# tricorder.net
KiCad netlist of a schematic drawn in EAGLE
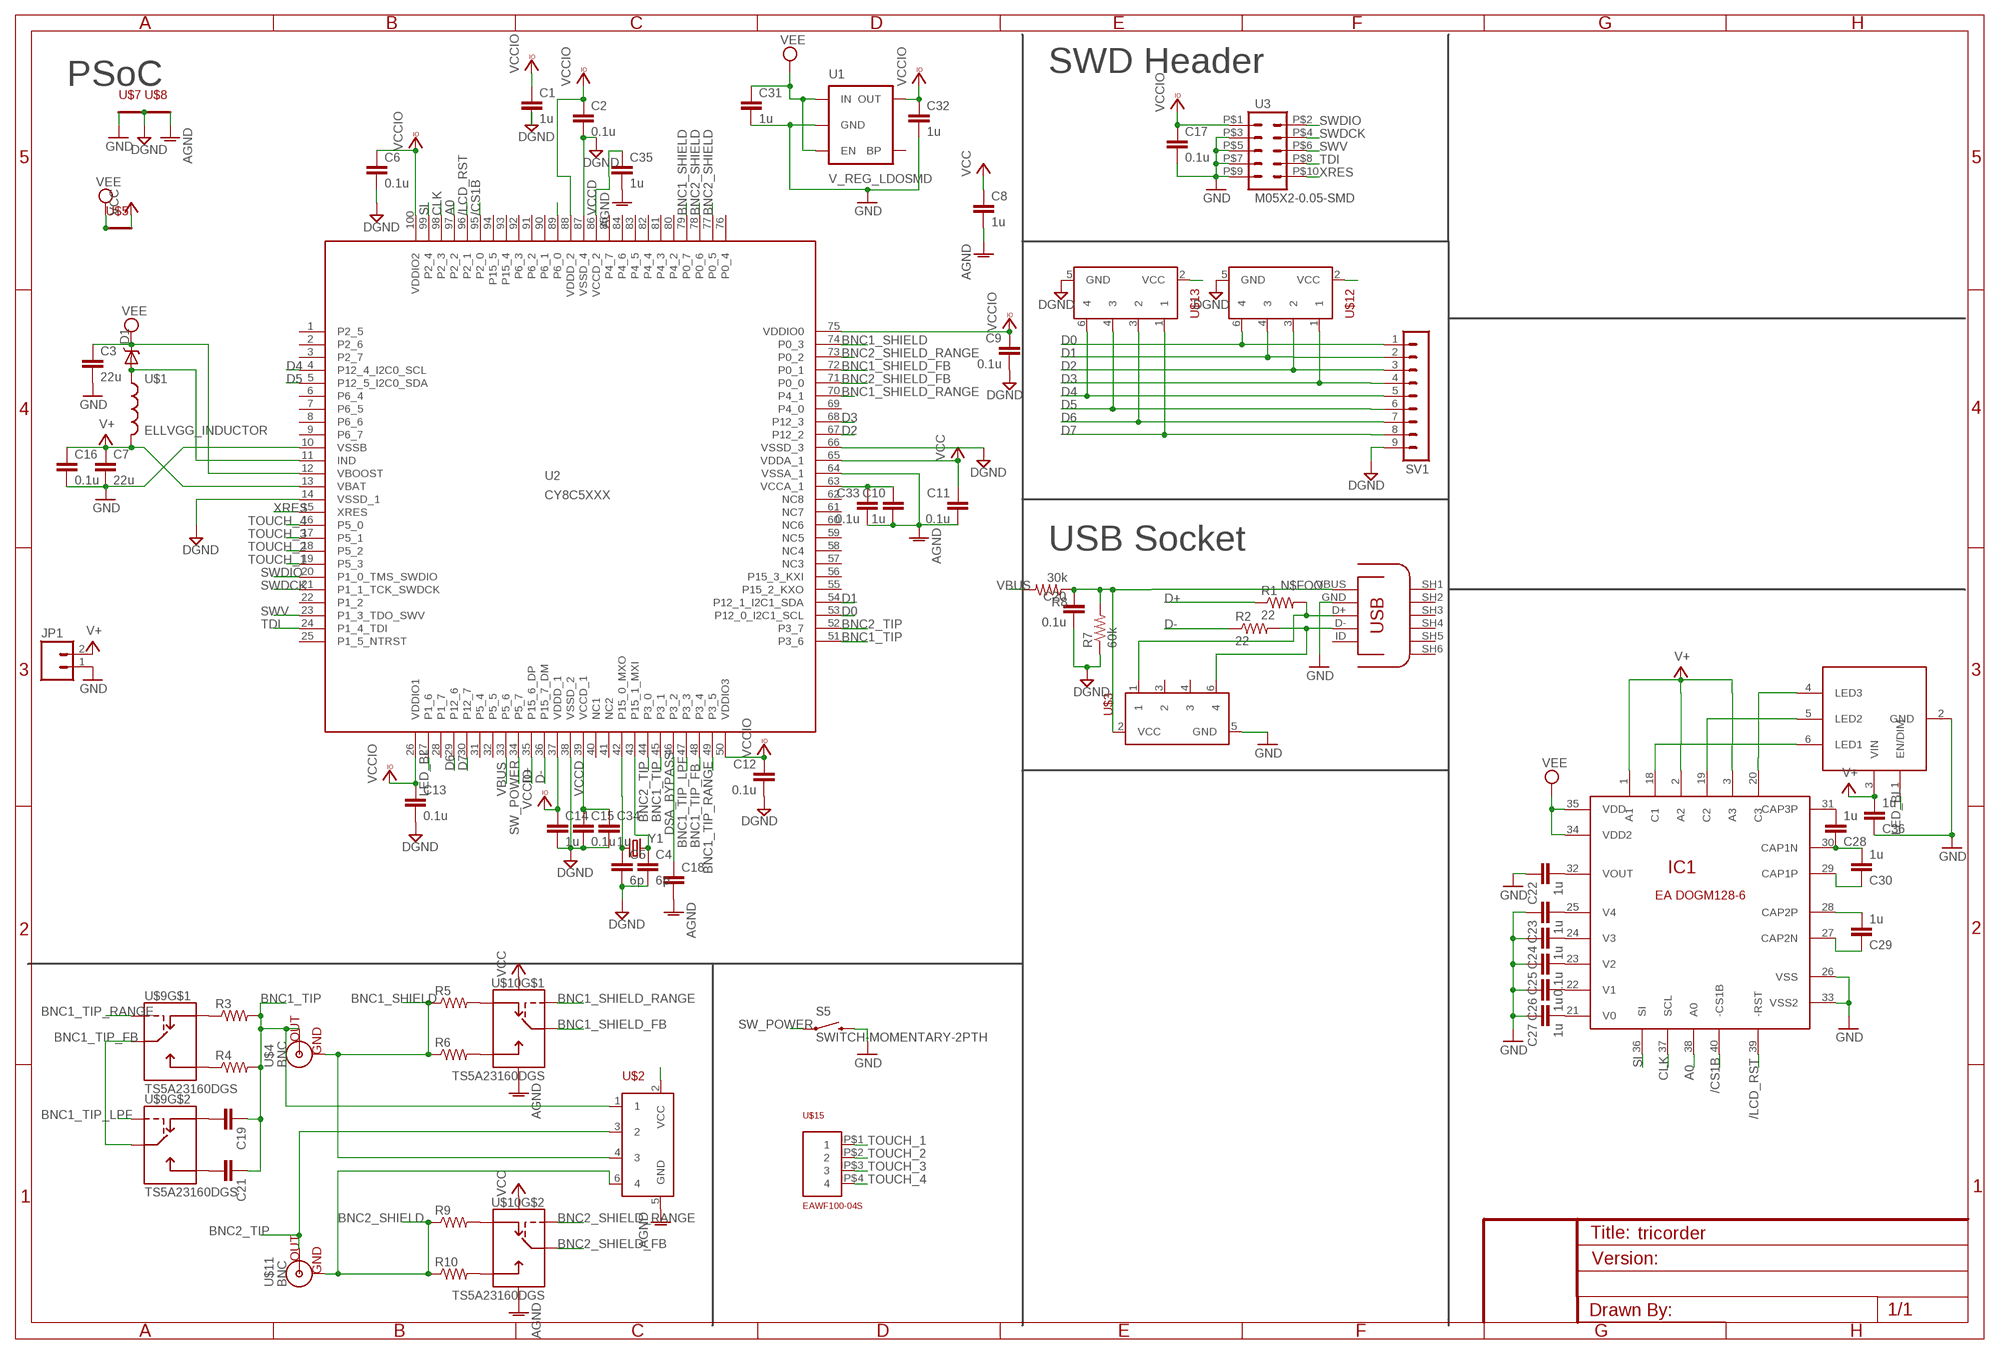
[diagram p0: schematic, sheet 1]

(export (version "E")
  (design (tool "Eeschema 10.0.6"))
  (components
    (comp (ref "C1")
      (value "1u")
      (footprint "eagle-import:0603-CAP")
      (libsource (lib "eagle-import") (part "CAP0603-CAP"))
    )
    (comp (ref "C2")
      (value "0.1u")
      (footprint "eagle-import:0603-CAP")
      (libsource (lib "eagle-import") (part "CAP0603-CAP"))
    )
    (comp (ref "C3")
      (value "22u")
      (footprint "eagle-import:0805")
      (libsource (lib "eagle-import") (part "CAP0805"))
    )
    (comp (ref "C4")
      (value "6p")
      (footprint "eagle-import:0603-CAP")
      (libsource (lib "eagle-import") (part "CAP0603-CAP"))
    )
    (comp (ref "C5")
      (value "6p")
      (footprint "eagle-import:0603-CAP")
      (libsource (lib "eagle-import") (part "CAP0603-CAP"))
    )
    (comp (ref "C6")
      (value "0.1u")
      (footprint "eagle-import:C0603K")
      (libsource (lib "eagle-import") (part "C-EUC0603K"))
    )
    (comp (ref "C7")
      (value "22u")
      (footprint "eagle-import:0805")
      (libsource (lib "eagle-import") (part "CAP0805"))
    )
    (comp (ref "C8")
      (value "1u")
      (footprint "eagle-import:0603-CAP")
      (libsource (lib "eagle-import") (part "CAP0603-CAP"))
    )
    (comp (ref "C9")
      (value "0.1u")
      (footprint "eagle-import:0603-CAP")
      (libsource (lib "eagle-import") (part "CAP0603-CAP"))
    )
    (comp (ref "C10")
      (value "1u")
      (footprint "eagle-import:0603-CAP")
      (libsource (lib "eagle-import") (part "CAP0603-CAP"))
    )
    (comp (ref "C11")
      (value "0.1u")
      (footprint "eagle-import:0603-CAP")
      (libsource (lib "eagle-import") (part "CAP0603-CAP"))
    )
    (comp (ref "C12")
      (value "0.1u")
      (footprint "eagle-import:C0603K")
      (libsource (lib "eagle-import") (part "C-EUC0603K"))
    )
    (comp (ref "C13")
      (value "0.1u")
      (footprint "eagle-import:C0603K")
      (libsource (lib "eagle-import") (part "C-EUC0603K"))
    )
    (comp (ref "C14")
      (value "1u")
      (footprint "eagle-import:0603-CAP")
      (libsource (lib "eagle-import") (part "CAP0603-CAP"))
    )
    (comp (ref "C15")
      (value "0.1u")
      (footprint "eagle-import:0603-CAP")
      (libsource (lib "eagle-import") (part "CAP0603-CAP"))
    )
    (comp (ref "C16")
      (value "0.1u")
      (footprint "eagle-import:0603-CAP")
      (libsource (lib "eagle-import") (part "CAP0603-CAP"))
    )
    (comp (ref "C17")
      (value "0.1u")
      (footprint "eagle-import:C0603K")
      (libsource (lib "eagle-import") (part "C-EUC0603K"))
    )
    (comp (ref "C18")
      (value "CAP0805")
      (footprint "eagle-import:0805")
      (libsource (lib "eagle-import") (part "CAP0805"))
    )
    (comp (ref "C19")
      (value "CAP0603-CAP")
      (footprint "eagle-import:0603-CAP")
      (libsource (lib "eagle-import") (part "CAP0603-CAP"))
    )
    (comp (ref "C20")
      (value "0.1u")
      (footprint "eagle-import:0603-CAP")
      (libsource (lib "eagle-import") (part "CAP0603-CAP"))
    )
    (comp (ref "C21")
      (value "CAP0603-CAP")
      (footprint "eagle-import:0603-CAP")
      (libsource (lib "eagle-import") (part "CAP0603-CAP"))
    )
    (comp (ref "C22")
      (value "1u")
      (footprint "eagle-import:C0603K")
      (libsource (lib "eagle-import") (part "C-EUC0603K"))
    )
    (comp (ref "C23")
      (value "1u")
      (footprint "eagle-import:C0603K")
      (libsource (lib "eagle-import") (part "C-EUC0603K"))
    )
    (comp (ref "C24")
      (value "1u")
      (footprint "eagle-import:C0603K")
      (libsource (lib "eagle-import") (part "C-EUC0603K"))
    )
    (comp (ref "C25")
      (value "0.1u")
      (footprint "eagle-import:C0603K")
      (libsource (lib "eagle-import") (part "C-EUC0603K"))
    )
    (comp (ref "C26")
      (value "1u")
      (footprint "eagle-import:C0603K")
      (libsource (lib "eagle-import") (part "C-EUC0603K"))
    )
    (comp (ref "C27")
      (value "1u")
      (footprint "eagle-import:C0603K")
      (libsource (lib "eagle-import") (part "C-EUC0603K"))
    )
    (comp (ref "C28")
      (value "1u")
      (footprint "eagle-import:C0603K")
      (libsource (lib "eagle-import") (part "C-EUC0603K"))
    )
    (comp (ref "C29")
      (value "1u")
      (footprint "eagle-import:C0603K")
      (libsource (lib "eagle-import") (part "C-EUC0603K"))
    )
    (comp (ref "C30")
      (value "1u")
      (footprint "eagle-import:C0603K")
      (libsource (lib "eagle-import") (part "C-EUC0603K"))
    )
    (comp (ref "C31")
      (value "1u")
      (footprint "eagle-import:0603-CAP")
      (libsource (lib "eagle-import") (part "CAP0603-CAP"))
    )
    (comp (ref "C32")
      (value "1u")
      (footprint "eagle-import:0603-CAP")
      (libsource (lib "eagle-import") (part "CAP0603-CAP"))
    )
    (comp (ref "C33")
      (value "0.1u")
      (footprint "eagle-import:0603-CAP")
      (libsource (lib "eagle-import") (part "CAP0603-CAP"))
    )
    (comp (ref "C34")
      (value "1u")
      (footprint "eagle-import:0603-CAP")
      (libsource (lib "eagle-import") (part "CAP0603-CAP"))
    )
    (comp (ref "C35")
      (value "1u")
      (footprint "eagle-import:0603-CAP")
      (libsource (lib "eagle-import") (part "CAP0603-CAP"))
    )
    (comp (ref "C36")
      (value "1u")
      (footprint "eagle-import:C0603K")
      (libsource (lib "eagle-import") (part "C-EUC0603K"))
    )
    (comp (ref "D1")
      (value "DIODE-SCHOTTKY_")
      (footprint "eagle-import:SMA-DIODE")
      (libsource (lib "eagle-import") (part "DIODE-SCHOTTKY_"))
    )
    (comp (ref "IC1")
      (value "EADOGM128")
      (footprint "eagle-import:EADOGM128")
      (libsource (lib "eagle-import") (part "EADOGM128"))
    )
    (comp (ref "JP1")
      (value "M02PTH")
      (footprint "eagle-import:1X02")
      (libsource (lib "eagle-import") (part "M02PTH"))
    )
    (comp (ref "R1")
      (value "22")
      (footprint "eagle-import:0603-RES")
      (libsource (lib "eagle-import") (part "RESISTOR0603-RES"))
    )
    (comp (ref "R2")
      (value "22")
      (footprint "eagle-import:0603-RES")
      (libsource (lib "eagle-import") (part "RESISTOR0603-RES"))
    )
    (comp (ref "R3")
      (value "RESISTOR0603-RES")
      (footprint "eagle-import:0603-RES")
      (libsource (lib "eagle-import") (part "RESISTOR0603-RES"))
    )
    (comp (ref "R4")
      (value "RESISTOR0603-RES")
      (footprint "eagle-import:0603-RES")
      (libsource (lib "eagle-import") (part "RESISTOR0603-RES"))
    )
    (comp (ref "R5")
      (value "RESISTOR0603-RES")
      (footprint "eagle-import:0603-RES")
      (libsource (lib "eagle-import") (part "RESISTOR0603-RES"))
    )
    (comp (ref "R6")
      (value "RESISTOR0603-RES")
      (footprint "eagle-import:0603-RES")
      (libsource (lib "eagle-import") (part "RESISTOR0603-RES"))
    )
    (comp (ref "R7")
      (value "60k")
      (footprint "eagle-import:0603-RES")
      (libsource (lib "eagle-import") (part "RESISTOR0603-RES"))
    )
    (comp (ref "R8")
      (value "30k")
      (footprint "eagle-import:0603-RES")
      (libsource (lib "eagle-import") (part "RESISTOR0603-RES"))
    )
    (comp (ref "R9")
      (value "RESISTOR0603-RES")
      (footprint "eagle-import:0603-RES")
      (libsource (lib "eagle-import") (part "RESISTOR0603-RES"))
    )
    (comp (ref "R10")
      (value "RESISTOR0603-RES")
      (footprint "eagle-import:0603-RES")
      (libsource (lib "eagle-import") (part "RESISTOR0603-RES"))
    )
    (comp (ref "S5")
      (value "SWITCH-MOMENTARY-2PTH")
      (footprint "eagle-import:TACTILE-PTH")
      (libsource (lib "eagle-import") (part "SWITCH-MOMENTARY-2PTH"))
    )
    (comp (ref "SV1")
      (value "MA09-1W")
      (footprint "eagle-import:MA09-1W")
      (libsource (lib "eagle-import") (part "MA09-1W"))
    )
    (comp (ref "U$1")
      (value "ELLVGG_INDUCTOR")
      (footprint "eagle-import:ELLVGG_INDUCTOR")
      (libsource (lib "eagle-import") (part "ELLVGG_INDUCTOR"))
    )
    (comp (ref "U$2")
      (value "ESD5V3U4RRSSOT363")
      (footprint "eagle-import:SOT363_INFINEON")
      (libsource (lib "eagle-import") (part "ESD5V3U4RRSSOT363"))
    )
    (comp (ref "U$3")
      (value "ESD5V3U4RRSSOT363")
      (footprint "eagle-import:SOT363_INFINEON")
      (libsource (lib "eagle-import") (part "ESD5V3U4RRSSOT363"))
    )
    (comp (ref "U$4")
      (value "BNC")
      (footprint "eagle-import:BNC_RA")
      (libsource (lib "eagle-import") (part "BNC"))
    )
    (comp (ref "U$5")
      (value "SHORT-2")
      (footprint "eagle-import:SHORT-2")
      (libsource (lib "eagle-import") (part "SHORT-2"))
    )
    (comp (ref "U$7")
      (value "SHORT-2")
      (footprint "eagle-import:SHORT-2")
      (libsource (lib "eagle-import") (part "SHORT-2"))
    )
    (comp (ref "U$8")
      (value "SHORT-2")
      (footprint "eagle-import:SHORT-2")
      (libsource (lib "eagle-import") (part "SHORT-2"))
    )
    (comp (ref "U$9")
      (value "TS5A23160DGS")
      (footprint "eagle-import:MSOP10")
      (libsource (lib "eagle-import") (part "TS5A23160DGS"))
    )
    (comp (ref "U$10")
      (value "TS5A23160DGS")
      (footprint "eagle-import:MSOP10")
      (libsource (lib "eagle-import") (part "TS5A23160DGS"))
    )
    (comp (ref "U$11")
      (value "BNC")
      (footprint "eagle-import:BNC_RA")
      (libsource (lib "eagle-import") (part "BNC"))
    )
    (comp (ref "U$12")
      (value "ESD5V3U4RRSSOT363")
      (footprint "eagle-import:SOT363_INFINEON")
      (libsource (lib "eagle-import") (part "ESD5V3U4RRSSOT363"))
    )
    (comp (ref "U$13")
      (value "ESD5V3U4RRSSOT363")
      (footprint "eagle-import:SOT363_INFINEON")
      (libsource (lib "eagle-import") (part "ESD5V3U4RRSSOT363"))
    )
    (comp (ref "U$15")
      (value "EAWF100-04S")
      (footprint "eagle-import:EAWF100-04S")
      (libsource (lib "eagle-import") (part "EAWF100-04S"))
    )
    (comp (ref "U$16")
      (value "CAT4003B")
      (footprint "eagle-import:SOT23-6")
      (libsource (lib "eagle-import") (part "CAT4003B"))
    )
    (comp (ref "U1")
      (value "V_REG_LDOSMD")
      (footprint "eagle-import:SOT23-5")
      (libsource (lib "eagle-import") (part "V_REG_LDOSMD"))
    )
    (comp (ref "U2")
      (value "CY8C5XXX")
      (footprint "eagle-import:TQFP-14X14-100")
      (fields (field (name "MPN") "CY8C3866AXI-040"))
      (libsource (lib "eagle-import") (part "CY8C3XXX-100PIN"))
    )
    (comp (ref "U3")
      (value "M05X2-0.05-SMD")
      (footprint "eagle-import:PINHD-2X5-0.05-SMD")
      (libsource (lib "eagle-import") (part "M05X2-0.05-SMD"))
    )
    (comp (ref "U7")
      (value "MICROUSB")
      (footprint "eagle-import:USB-MICROB")
      (libsource (lib "eagle-import") (part "MICROUSB"))
    )
    (comp (ref "Y1")
      (value "XRCGB_XTAL")
      (footprint "eagle-import:XRCGB-XTAL")
      (libsource (lib "eagle-import") (part "XRCGB_XTAL"))
    )
  )
  (nets
    (net (code "1") (name "/A0") (class "Default")
      (node (ref "IC1") (pin "38") (pinfunction "A0_38") (pintype "input"))
      (node (ref "U2") (pin "97") (pinfunction "P2_2_97") (pintype "passive"))
    )
    (net (code "2") (name "/BNC1_SHIELD") (class "Default")
      (node (ref "R5") (pin "1") (pinfunction "1_1") (pintype "passive"))
      (node (ref "R6") (pin "1") (pinfunction "1_1") (pintype "passive"))
      (node (ref "U$2") (pin "4") (pinfunction "3_4") (pintype "passive"))
      (node (ref "U$4") (pin "SHIELD_1") (pinfunction "GND_SHIELD_1") (pintype "bidirectional"))
      (node (ref "U$4") (pin "SHIELD_2") (pinfunction "GND_SHIELD_2") (pintype "bidirectional"))
      (node (ref "U2") (pin "74") (pinfunction "P0_3_74") (pintype "passive"))
      (node (ref "U2") (pin "79") (pinfunction "P0_7_79") (pintype "passive"))
    )
    (net (code "3") (name "/BNC1_SHIELD_FB") (class "Default")
      (node (ref "U$10") (pin "10") (pinfunction "COM_10") (pintype "passive"))
      (node (ref "U2") (pin "72") (pinfunction "P0_1_72") (pintype "passive"))
    )
    (net (code "4") (name "/BNC1_SHIELD_RANGE") (class "Default")
      (node (ref "U$10") (pin "1") (pinfunction "IN_1") (pintype "input"))
      (node (ref "U2") (pin "70") (pinfunction "P4_1_70") (pintype "passive"))
    )
    (net (code "5") (name "/BNC1_TIP") (class "Default")
      (node (ref "C19") (pin "1") (pinfunction "1_1") (pintype "passive"))
      (node (ref "C21") (pin "1") (pinfunction "1_1") (pintype "passive"))
      (node (ref "R3") (pin "2") (pinfunction "2_2") (pintype "passive"))
      (node (ref "R4") (pin "2") (pinfunction "2_2") (pintype "passive"))
      (node (ref "U$2") (pin "1") (pinfunction "1_1") (pintype "passive"))
      (node (ref "U$4") (pin "TIP") (pinfunction "OUT_TIP") (pintype "bidirectional"))
      (node (ref "U2") (pin "45") (pinfunction "P3_1_45") (pintype "passive"))
      (node (ref "U2") (pin "51") (pinfunction "P3_6_51") (pintype "passive"))
    )
    (net (code "6") (name "/BNC1_TIP_FB") (class "Default")
      (node (ref "U$9") (pin "10") (pinfunction "COM_10") (pintype "passive"))
      (node (ref "U$9") (pin "6") (pinfunction "COM_6") (pintype "passive"))
      (node (ref "U2") (pin "48") (pinfunction "P3_4_48") (pintype "passive"))
    )
    (net (code "7") (name "/BNC1_TIP_LPF") (class "Default")
      (node (ref "U$9") (pin "5") (pinfunction "IN_5") (pintype "input"))
      (node (ref "U2") (pin "47") (pinfunction "P3_3_47") (pintype "passive"))
    )
    (net (code "8") (name "/BNC1_TIP_RANGE") (class "Default")
      (node (ref "U$9") (pin "1") (pinfunction "IN_1") (pintype "input"))
      (node (ref "U2") (pin "49") (pinfunction "P3_5_49") (pintype "passive"))
    )
    (net (code "9") (name "/BNC2_SHIELD") (class "Default")
      (node (ref "R10") (pin "1") (pinfunction "1_1") (pintype "passive"))
      (node (ref "R9") (pin "1") (pinfunction "1_1") (pintype "passive"))
      (node (ref "U$11") (pin "SHIELD_1") (pinfunction "GND_SHIELD_1") (pintype "bidirectional"))
      (node (ref "U$11") (pin "SHIELD_2") (pinfunction "GND_SHIELD_2") (pintype "bidirectional"))
      (node (ref "U$2") (pin "6") (pinfunction "4_6") (pintype "passive"))
      (node (ref "U2") (pin "77") (pinfunction "P0_5_77") (pintype "passive"))
      (node (ref "U2") (pin "78") (pinfunction "P0_6_78") (pintype "passive"))
    )
    (net (code "10") (name "/BNC2_SHIELD_FB") (class "Default")
      (node (ref "U$10") (pin "6") (pinfunction "COM_6") (pintype "passive"))
      (node (ref "U2") (pin "71") (pinfunction "P0_0_71") (pintype "passive"))
    )
    (net (code "11") (name "/BNC2_SHIELD_RANGE") (class "Default")
      (node (ref "U$10") (pin "5") (pinfunction "IN_5") (pintype "input"))
      (node (ref "U2") (pin "73") (pinfunction "P0_2_73") (pintype "passive"))
    )
    (net (code "12") (name "/BNC2_TIP") (class "Default")
      (node (ref "U$11") (pin "TIP") (pinfunction "OUT_TIP") (pintype "bidirectional"))
      (node (ref "U$2") (pin "3") (pinfunction "2_3") (pintype "passive"))
      (node (ref "U2") (pin "44") (pinfunction "P3_0_44") (pintype "passive"))
      (node (ref "U2") (pin "52") (pinfunction "P3_7_52") (pintype "passive"))
    )
    (net (code "13") (name "/CLK") (class "Default")
      (node (ref "IC1") (pin "37") (pinfunction "SCL_37") (pintype "input"))
      (node (ref "U2") (pin "98") (pinfunction "P2_3_98") (pintype "passive"))
    )
    (net (code "14") (name "/D+") (class "Default")
      (node (ref "R1") (pin "1") (pinfunction "1_1") (pintype "passive"))
      (node (ref "U2") (pin "35") (pinfunction "P15_6_DP_35") (pintype "passive"))
    )
    (net (code "15") (name "/D-") (class "Default")
      (node (ref "R2") (pin "1") (pinfunction "1_1") (pintype "passive"))
      (node (ref "U2") (pin "36") (pinfunction "P15_7_DM_36") (pintype "passive"))
    )
    (net (code "16") (name "/D0") (class "Default")
      (node (ref "SV1") (pin "1") (pinfunction "1_1") (pintype "passive"))
      (node (ref "U$12") (pin "6") (pinfunction "4_6") (pintype "passive"))
      (node (ref "U2") (pin "53") (pinfunction "P12_0_I2C1_SCL_53") (pintype "passive"))
    )
    (net (code "17") (name "/D1") (class "Default")
      (node (ref "SV1") (pin "2") (pinfunction "2_2") (pintype "passive"))
      (node (ref "U$12") (pin "4") (pinfunction "3_4") (pintype "passive"))
      (node (ref "U2") (pin "54") (pinfunction "P12_1_I2C1_SDA_54") (pintype "passive"))
    )
    (net (code "18") (name "/D2") (class "Default")
      (node (ref "SV1") (pin "3") (pinfunction "3_3") (pintype "passive"))
      (node (ref "U$12") (pin "3") (pinfunction "2_3") (pintype "passive"))
      (node (ref "U2") (pin "67") (pinfunction "P12_2_67") (pintype "passive"))
    )
    (net (code "19") (name "/D3") (class "Default")
      (node (ref "SV1") (pin "4") (pinfunction "4_4") (pintype "passive"))
      (node (ref "U$12") (pin "1") (pinfunction "1_1") (pintype "passive"))
      (node (ref "U2") (pin "68") (pinfunction "P12_3_68") (pintype "passive"))
    )
    (net (code "20") (name "/D4") (class "Default")
      (node (ref "SV1") (pin "5") (pinfunction "5_5") (pintype "passive"))
      (node (ref "U$13") (pin "6") (pinfunction "4_6") (pintype "passive"))
      (node (ref "U2") (pin "4") (pinfunction "P12_4_I2C0_SCL_4") (pintype "passive"))
    )
    (net (code "21") (name "/D5") (class "Default")
      (node (ref "SV1") (pin "6") (pinfunction "6_6") (pintype "passive"))
      (node (ref "U$13") (pin "4") (pinfunction "3_4") (pintype "passive"))
      (node (ref "U2") (pin "5") (pinfunction "P12_5_I2C0_SDA_5") (pintype "passive"))
    )
    (net (code "22") (name "/D6") (class "Default")
      (node (ref "SV1") (pin "7") (pinfunction "7_7") (pintype "passive"))
      (node (ref "U$13") (pin "3") (pinfunction "2_3") (pintype "passive"))
      (node (ref "U2") (pin "29") (pinfunction "P12_6_29") (pintype "passive"))
    )
    (net (code "23") (name "/D7") (class "Default")
      (node (ref "SV1") (pin "8") (pinfunction "8_8") (pintype "passive"))
      (node (ref "U$13") (pin "1") (pinfunction "1_1") (pintype "passive"))
      (node (ref "U2") (pin "30") (pinfunction "P12_7_30") (pintype "passive"))
    )
    (net (code "24") (name "/DSA_BYPASS") (class "Default")
      (node (ref "C18") (pin "1") (pinfunction "1_1") (pintype "passive"))
      (node (ref "U2") (pin "46") (pinfunction "P3_2_46") (pintype "passive"))
    )
    (net (code "25") (name "/LED_BL") (class "Default")
      (node (ref "U$16") (pin "1") (pinfunction "EN/DIM_1") (pintype "input"))
      (node (ref "U2") (pin "27") (pinfunction "P1_6_27") (pintype "passive"))
    )
    (net (code "26") (name "/N$FOO") (class "Default")
      (node (ref "C20") (pin "1") (pinfunction "1_1") (pintype "passive"))
      (node (ref "R7") (pin "2") (pinfunction "2_2") (pintype "passive"))
      (node (ref "R8") (pin "1") (pinfunction "1_1") (pintype "passive"))
      (node (ref "U$3") (pin "2") (pinfunction "VCC_2") (pintype "power_in"))
      (node (ref "U7") (pin "VBUS") (pinfunction "VCC_VBUS") (pintype "bidirectional"))
    )
    (net (code "27") (name "/SI") (class "Default")
      (node (ref "IC1") (pin "36") (pinfunction "SI_36") (pintype "input"))
      (node (ref "U2") (pin "99") (pinfunction "P2_4_99") (pintype "passive"))
    )
    (net (code "28") (name "/SWDCK") (class "Default")
      (node (ref "U2") (pin "21") (pinfunction "P1_1_TCK_SWDCK_21") (pintype "passive"))
      (node (ref "U3") (pin "P$4") (pinfunction "4_P$4") (pintype "passive"))
    )
    (net (code "29") (name "/SWDIO") (class "Default")
      (node (ref "U2") (pin "20") (pinfunction "P1_0_TMS_SWDIO_20") (pintype "passive"))
      (node (ref "U3") (pin "P$2") (pinfunction "2_P$2") (pintype "passive"))
    )
    (net (code "30") (name "/SWV") (class "Default")
      (node (ref "U2") (pin "23") (pinfunction "P1_3_TDO_SWV_23") (pintype "passive"))
      (node (ref "U3") (pin "P$6") (pinfunction "6_P$6") (pintype "passive"))
    )
    (net (code "31") (name "/SW_POWER") (class "Default")
      (node (ref "S5") (pin "1") (pinfunction "1_1") (pintype "passive"))
      (node (ref "U2") (pin "34") (pinfunction "P5_7_34") (pintype "passive"))
    )
    (net (code "32") (name "/TDI") (class "Default")
      (node (ref "U2") (pin "24") (pinfunction "P1_4_TDI_24") (pintype "passive"))
      (node (ref "U3") (pin "P$8") (pinfunction "8_P$8") (pintype "passive"))
    )
    (net (code "33") (name "/TOUCH_1") (class "Default")
      (node (ref "U$15") (pin "P$1") (pinfunction "1_P$1") (pintype "bidirectional"))
      (node (ref "U2") (pin "19") (pinfunction "P5_3_19") (pintype "passive"))
    )
    (net (code "34") (name "/TOUCH_2") (class "Default")
      (node (ref "U$15") (pin "P$2") (pinfunction "2_P$2") (pintype "bidirectional"))
      (node (ref "U2") (pin "18") (pinfunction "P5_2_18") (pintype "passive"))
    )
    (net (code "35") (name "/TOUCH_3") (class "Default")
      (node (ref "U$15") (pin "P$3") (pinfunction "3_P$3") (pintype "bidirectional"))
      (node (ref "U2") (pin "17") (pinfunction "P5_1_17") (pintype "passive"))
    )
    (net (code "36") (name "/TOUCH_4") (class "Default")
      (node (ref "U$15") (pin "P$4") (pinfunction "4_P$4") (pintype "bidirectional"))
      (node (ref "U2") (pin "16") (pinfunction "P5_0_16") (pintype "passive"))
    )
    (net (code "37") (name "/VBUS") (class "Default")
      (node (ref "R8") (pin "2") (pinfunction "2_2") (pintype "passive"))
      (node (ref "U2") (pin "33") (pinfunction "P5_6_33") (pintype "passive"))
    )
    (net (code "38") (name "/VCCD") (class "Default")
      (node (ref "C15") (pin "1") (pinfunction "1_1") (pintype "passive"))
      (node (ref "C34") (pin "1") (pinfunction "1_1") (pintype "passive"))
      (node (ref "C35") (pin "1") (pinfunction "1_1") (pintype "passive"))
      (node (ref "U2") (pin "39") (pinfunction "VCCD_1_39") (pintype "passive"))
      (node (ref "U2") (pin "86") (pinfunction "VCCD_2_86") (pintype "passive"))
    )
    (net (code "39") (name "/XRES") (class "Default")
      (node (ref "U2") (pin "15") (pinfunction "XRES_15") (pintype "passive"))
      (node (ref "U3") (pin "P$10") (pinfunction "10_P$10") (pintype "passive"))
    )
    (net (code "40") (name "/{slash}CS1B") (class "Default")
      (node (ref "IC1") (pin "40") (pinfunction "-CS1B_40") (pintype "input"))
      (node (ref "U2") (pin "95") (pinfunction "P2_0_95") (pintype "passive"))
    )
    (net (code "41") (name "/{slash}LCD_RST") (class "Default")
      (node (ref "IC1") (pin "39") (pinfunction "-RST_39") (pintype "input"))
      (node (ref "U2") (pin "96") (pinfunction "P2_1_96") (pintype "passive"))
    )
    (net (code "42") (name "AGND") (class "Default")
      (node (ref "C10") (pin "2") (pinfunction "2_2") (pintype "passive"))
      (node (ref "C11") (pin "2") (pinfunction "2_2") (pintype "passive"))
      (node (ref "C18") (pin "2") (pinfunction "2_2") (pintype "passive"))
      (node (ref "C33") (pin "2") (pinfunction "2_2") (pintype "passive"))
      (node (ref "C35") (pin "2") (pinfunction "2_2") (pintype "passive"))
      (node (ref "C8") (pin "2") (pinfunction "2_2") (pintype "passive"))
      (node (ref "U$10") (pin "3") (pinfunction "GND_3") (pintype "power_in"))
      (node (ref "U$2") (pin "5") (pinfunction "GND_5") (pintype "power_in"))
      (node (ref "U$8") (pin "P$2") (pinfunction "P$2_P$2") (pintype "passive"))
      (node (ref "U$9") (pin "3") (pinfunction "GND_3") (pintype "power_in"))
      (node (ref "U2") (pin "64") (pinfunction "VSSA_1_64") (pintype "passive"))
    )
    (net (code "43") (name "DGND") (class "Default")
      (node (ref "C1") (pin "2") (pinfunction "2_2") (pintype "passive"))
      (node (ref "C12") (pin "2") (pinfunction "2_2") (pintype "passive"))
      (node (ref "C13") (pin "2") (pinfunction "2_2") (pintype "passive"))
      (node (ref "C14") (pin "2") (pinfunction "2_2") (pintype "passive"))
      (node (ref "C15") (pin "2") (pinfunction "2_2") (pintype "passive"))
      (node (ref "C2") (pin "2") (pinfunction "2_2") (pintype "passive"))
      (node (ref "C20") (pin "2") (pinfunction "2_2") (pintype "passive"))
      (node (ref "C34") (pin "2") (pinfunction "2_2") (pintype "passive"))
      (node (ref "C4") (pin "2") (pinfunction "2_2") (pintype "passive"))
      (node (ref "C5") (pin "2") (pinfunction "2_2") (pintype "passive"))
      (node (ref "C6") (pin "2") (pinfunction "2_2") (pintype "passive"))
      (node (ref "C9") (pin "2") (pinfunction "2_2") (pintype "passive"))
      (node (ref "R7") (pin "1") (pinfunction "1_1") (pintype "passive"))
      (node (ref "SV1") (pin "9") (pinfunction "9_9") (pintype "passive"))
      (node (ref "U$12") (pin "5") (pinfunction "GND_5") (pintype "power_in"))
      (node (ref "U$13") (pin "5") (pinfunction "GND_5") (pintype "power_in"))
      (node (ref "U$7") (pin "P$2") (pinfunction "P$2_P$2") (pintype "passive"))
      (node (ref "U$8") (pin "P$1") (pinfunction "P$1_P$1") (pintype "passive"))
      (node (ref "U2") (pin "14") (pinfunction "VSSD_1_14") (pintype "passive"))
      (node (ref "U2") (pin "38") (pinfunction "VSSD_2_38") (pintype "passive"))
      (node (ref "U2") (pin "66") (pinfunction "VSSD_3_66") (pintype "passive"))
      (node (ref "U2") (pin "87") (pinfunction "VSSD_4_87") (pintype "passive"))
    )
    (net (code "44") (name "GND") (class "Default")
      (node (ref "C16") (pin "2") (pinfunction "2_2") (pintype "passive"))
      (node (ref "C17") (pin "2") (pinfunction "2_2") (pintype "passive"))
      (node (ref "C22") (pin "1") (pinfunction "1_1") (pintype "passive"))
      (node (ref "C23") (pin "1") (pinfunction "1_1") (pintype "passive"))
      (node (ref "C24") (pin "1") (pinfunction "1_1") (pintype "passive"))
      (node (ref "C25") (pin "1") (pinfunction "1_1") (pintype "passive"))
      (node (ref "C26") (pin "1") (pinfunction "1_1") (pintype "passive"))
      (node (ref "C27") (pin "1") (pinfunction "1_1") (pintype "passive"))
      (node (ref "C3") (pin "2") (pinfunction "2_2") (pintype "passive"))
      (node (ref "C31") (pin "2") (pinfunction "2_2") (pintype "passive"))
      (node (ref "C32") (pin "2") (pinfunction "2_2") (pintype "passive"))
      (node (ref "C36") (pin "1") (pinfunction "1_1") (pintype "passive"))
      (node (ref "C7") (pin "2") (pinfunction "2_2") (pintype "passive"))
      (node (ref "IC1") (pin "26") (pinfunction "VSS_26") (pintype "power_in"))
      (node (ref "IC1") (pin "33") (pinfunction "VSS2_33") (pintype "power_in"))
      (node (ref "JP1") (pin "1") (pinfunction "1_1") (pintype "passive"))
      (node (ref "S5") (pin "3") (pinfunction "2_3") (pintype "passive"))
      (node (ref "U$16") (pin "2") (pinfunction "GND_2") (pintype "power_in"))
      (node (ref "U$3") (pin "5") (pinfunction "GND_5") (pintype "power_in"))
      (node (ref "U$7") (pin "P$1") (pinfunction "P$1_P$1") (pintype "passive"))
      (node (ref "U1") (pin "2") (pinfunction "GND_2") (pintype "input"))
      (node (ref "U2") (pin "10") (pinfunction "VSSB_10") (pintype "passive"))
      (node (ref "U3") (pin "P$3") (pinfunction "3_P$3") (pintype "passive"))
      (node (ref "U3") (pin "P$5") (pinfunction "5_P$5") (pintype "passive"))
      (node (ref "U3") (pin "P$7") (pinfunction "7_P$7") (pintype "passive"))
      (node (ref "U3") (pin "P$9") (pinfunction "9_P$9") (pintype "passive"))
      (node (ref "U7") (pin "GND") (pinfunction "GND_GND") (pintype "bidirectional"))
    )
    (net (code "45") (name "Net-(IC1-C1)") (class "Default")
      (node (ref "IC1") (pin "18") (pinfunction "C1_18") (pintype "passive"))
      (node (ref "U$16") (pin "6") (pinfunction "LED1_6") (pintype "power_in"))
    )
    (net (code "46") (name "Net-(IC1-C2)") (class "Default")
      (node (ref "IC1") (pin "19") (pinfunction "C2_19") (pintype "passive"))
      (node (ref "U$16") (pin "5") (pinfunction "LED2_5") (pintype "power_in"))
    )
    (net (code "47") (name "Net-(IC1-C3)") (class "Default")
      (node (ref "IC1") (pin "20") (pinfunction "C3_20") (pintype "passive"))
      (node (ref "U$16") (pin "4") (pinfunction "LED3_4") (pintype "power_in"))
    )
    (net (code "48") (name "Net-(IC1-CAP1N)") (class "Default")
      (node (ref "C28") (pin "1") (pinfunction "1_1") (pintype "passive"))
      (node (ref "C30") (pin "2") (pinfunction "2_2") (pintype "passive"))
      (node (ref "IC1") (pin "30") (pinfunction "CAP1N_30") (pintype "passive"))
    )
    (net (code "49") (name "Net-(IC1-CAP1P)") (class "Default")
      (node (ref "C30") (pin "1") (pinfunction "1_1") (pintype "passive"))
      (node (ref "IC1") (pin "29") (pinfunction "CAP1P_29") (pintype "passive"))
    )
    (net (code "50") (name "Net-(IC1-CAP2N)") (class "Default")
      (node (ref "C29") (pin "1") (pinfunction "1_1") (pintype "passive"))
      (node (ref "IC1") (pin "27") (pinfunction "CAP2N_27") (pintype "passive"))
    )
    (net (code "51") (name "Net-(IC1-CAP2P)") (class "Default")
      (node (ref "C29") (pin "2") (pinfunction "2_2") (pintype "passive"))
      (node (ref "IC1") (pin "28") (pinfunction "CAP2P_28") (pintype "passive"))
    )
    (net (code "52") (name "Net-(IC1-CAP3P)") (class "Default")
      (node (ref "C28") (pin "2") (pinfunction "2_2") (pintype "passive"))
      (node (ref "IC1") (pin "31") (pinfunction "CAP3P_31") (pintype "passive"))
    )
    (net (code "53") (name "Net-(IC1-V0)") (class "Default")
      (node (ref "C27") (pin "2") (pinfunction "2_2") (pintype "passive"))
      (node (ref "IC1") (pin "21") (pinfunction "V0_21") (pintype "passive"))
    )
    (net (code "54") (name "Net-(IC1-V1)") (class "Default")
      (node (ref "C26") (pin "2") (pinfunction "2_2") (pintype "passive"))
      (node (ref "IC1") (pin "22") (pinfunction "V1_22") (pintype "passive"))
    )
    (net (code "55") (name "Net-(IC1-V2)") (class "Default")
      (node (ref "C25") (pin "2") (pinfunction "2_2") (pintype "passive"))
      (node (ref "IC1") (pin "23") (pinfunction "V2_23") (pintype "passive"))
    )
    (net (code "56") (name "Net-(IC1-V3)") (class "Default")
      (node (ref "C24") (pin "2") (pinfunction "2_2") (pintype "passive"))
      (node (ref "IC1") (pin "24") (pinfunction "V3_24") (pintype "passive"))
    )
    (net (code "57") (name "Net-(IC1-V4)") (class "Default")
      (node (ref "C23") (pin "2") (pinfunction "2_2") (pintype "passive"))
      (node (ref "IC1") (pin "25") (pinfunction "V4_25") (pintype "passive"))
    )
    (net (code "58") (name "Net-(IC1-VOUT)") (class "Default")
      (node (ref "C22") (pin "2") (pinfunction "2_2") (pintype "passive"))
      (node (ref "IC1") (pin "32") (pinfunction "VOUT_32") (pintype "passive"))
    )
    (net (code "59") (name "Net-(R1-Pad2)") (class "Default")
      (node (ref "R1") (pin "2") (pinfunction "2_2") (pintype "passive"))
      (node (ref "U$3") (pin "1") (pinfunction "1_1") (pintype "passive"))
      (node (ref "U7") (pin "D+") (pinfunction "D+_D+") (pintype "bidirectional"))
    )
    (net (code "60") (name "Net-(U$1-1)") (class "Default")
      (node (ref "D1") (pin "A") (pinfunction "A_A") (pintype "passive"))
      (node (ref "U$1") (pin "P$1") (pinfunction "1_P$1") (pintype "passive"))
      (node (ref "U2") (pin "11") (pinfunction "IND_11") (pintype "passive"))
    )
    (net (code "61") (name "Net-(U$3-4)") (class "Default")
      (node (ref "R2") (pin "2") (pinfunction "2_2") (pintype "passive"))
      (node (ref "U$3") (pin "6") (pinfunction "4_6") (pintype "passive"))
      (node (ref "U7") (pin "D-") (pinfunction "D-_D-") (pintype "bidirectional"))
    )
    (net (code "62") (name "Net-(U$9A-NC)") (class "Default")
      (node (ref "R3") (pin "1") (pinfunction "1_1") (pintype "passive"))
      (node (ref "U$9") (pin "9") (pinfunction "NC_9") (pintype "passive"))
    )
    (net (code "63") (name "Net-(U$9A-NO)") (class "Default")
      (node (ref "R4") (pin "1") (pinfunction "1_1") (pintype "passive"))
      (node (ref "U$9") (pin "2") (pinfunction "NO_2") (pintype "passive"))
    )
    (net (code "64") (name "Net-(U$9B-NC)") (class "Default")
      (node (ref "C19") (pin "2") (pinfunction "2_2") (pintype "passive"))
      (node (ref "U$9") (pin "7") (pinfunction "NC_7") (pintype "passive"))
    )
    (net (code "65") (name "Net-(U$9B-NO)") (class "Default")
      (node (ref "C21") (pin "2") (pinfunction "2_2") (pintype "passive"))
      (node (ref "U$9") (pin "4") (pinfunction "NO_4") (pintype "passive"))
    )
    (net (code "66") (name "Net-(U$10A-NC)") (class "Default")
      (node (ref "R5") (pin "2") (pinfunction "2_2") (pintype "passive"))
      (node (ref "U$10") (pin "9") (pinfunction "NC_9") (pintype "passive"))
    )
    (net (code "67") (name "Net-(U$10A-NO)") (class "Default")
      (node (ref "R6") (pin "2") (pinfunction "2_2") (pintype "passive"))
      (node (ref "U$10") (pin "2") (pinfunction "NO_2") (pintype "passive"))
    )
    (net (code "68") (name "Net-(U$10B-NC)") (class "Default")
      (node (ref "R9") (pin "2") (pinfunction "2_2") (pintype "passive"))
      (node (ref "U$10") (pin "7") (pinfunction "NC_7") (pintype "passive"))
    )
    (net (code "69") (name "Net-(U$10B-NO)") (class "Default")
      (node (ref "R10") (pin "2") (pinfunction "2_2") (pintype "passive"))
      (node (ref "U$10") (pin "4") (pinfunction "NO_4") (pintype "passive"))
    )
    (net (code "70") (name "Net-(U2-P15_0_MXO)") (class "Default")
      (node (ref "C5") (pin "1") (pinfunction "1_1") (pintype "passive"))
      (node (ref "U2") (pin "42") (pinfunction "P15_0_MXO_42") (pintype "passive"))
      (node (ref "Y1") (pin "1") (pinfunction "1_1") (pintype "passive"))
    )
    (net (code "71") (name "Net-(U2-P15_1_MXI)") (class "Default")
      (node (ref "C4") (pin "1") (pinfunction "1_1") (pintype "passive"))
      (node (ref "U2") (pin "43") (pinfunction "P15_1_MXI_43") (pintype "passive"))
      (node (ref "Y1") (pin "2") (pinfunction "2_2") (pintype "passive"))
    )
    (net (code "72") (name "Net-(U2-VCCA_1)") (class "Default")
      (node (ref "C10") (pin "1") (pinfunction "1_1") (pintype "passive"))
      (node (ref "C33") (pin "1") (pinfunction "1_1") (pintype "passive"))
      (node (ref "U2") (pin "63") (pinfunction "VCCA_1_63") (pintype "passive"))
    )
    (net (code "73") (name "V+") (class "Default")
      (node (ref "C16") (pin "1") (pinfunction "1_1") (pintype "passive"))
      (node (ref "C36") (pin "2") (pinfunction "2_2") (pintype "passive"))
      (node (ref "C7") (pin "1") (pinfunction "1_1") (pintype "passive"))
      (node (ref "IC1") (pin "1") (pinfunction "A1_1") (pintype "passive"))
      (node (ref "IC1") (pin "2") (pinfunction "A2_2") (pintype "passive"))
      (node (ref "IC1") (pin "3") (pinfunction "A3_3") (pintype "passive"))
      (node (ref "JP1") (pin "2") (pinfunction "2_2") (pintype "passive"))
      (node (ref "U$1") (pin "P$2") (pinfunction "2_P$2") (pintype "passive"))
      (node (ref "U$16") (pin "3") (pinfunction "VIN_3") (pintype "power_in"))
      (node (ref "U2") (pin "13") (pinfunction "VBAT_13") (pintype "passive"))
    )
    (net (code "74") (name "VCC") (class "Default")
      (node (ref "C11") (pin "1") (pinfunction "1_1") (pintype "passive"))
      (node (ref "C8") (pin "1") (pinfunction "1_1") (pintype "passive"))
      (node (ref "U$10") (pin "8") (pinfunction "VCC_8") (pintype "power_in"))
      (node (ref "U$5") (pin "P$2") (pinfunction "P$2_P$2") (pintype "passive"))
      (node (ref "U$9") (pin "8") (pinfunction "VCC_8") (pintype "power_in"))
      (node (ref "U2") (pin "65") (pinfunction "VDDA_1_65") (pintype "passive"))
    )
    (net (code "75") (name "VCCIO") (class "Default")
      (node (ref "C1") (pin "1") (pinfunction "1_1") (pintype "passive"))
      (node (ref "C12") (pin "1") (pinfunction "1_1") (pintype "passive"))
      (node (ref "C13") (pin "1") (pinfunction "1_1") (pintype "passive"))
      (node (ref "C14") (pin "1") (pinfunction "1_1") (pintype "passive"))
      (node (ref "C17") (pin "1") (pinfunction "1_1") (pintype "passive"))
      (node (ref "C2") (pin "1") (pinfunction "1_1") (pintype "passive"))
      (node (ref "C32") (pin "1") (pinfunction "1_1") (pintype "passive"))
      (node (ref "C6") (pin "1") (pinfunction "1_1") (pintype "passive"))
      (node (ref "C9") (pin "1") (pinfunction "1_1") (pintype "passive"))
      (node (ref "U1") (pin "5") (pinfunction "OUT_5") (pintype "passive"))
      (node (ref "U2") (pin "100") (pinfunction "VDDIO2_100") (pintype "passive"))
      (node (ref "U2") (pin "26") (pinfunction "VDDIO1_26") (pintype "passive"))
      (node (ref "U2") (pin "37") (pinfunction "VDDD_1_37") (pintype "passive"))
      (node (ref "U2") (pin "50") (pinfunction "VDDIO3_50") (pintype "passive"))
      (node (ref "U2") (pin "75") (pinfunction "VDDIO0_75") (pintype "passive"))
      (node (ref "U2") (pin "88") (pinfunction "VDDD_2_88") (pintype "passive"))
      (node (ref "U3") (pin "P$1") (pinfunction "1_P$1") (pintype "passive"))
    )
    (net (code "76") (name "VEE") (class "Default")
      (node (ref "C3") (pin "1") (pinfunction "1_1") (pintype "passive"))
      (node (ref "C31") (pin "1") (pinfunction "1_1") (pintype "passive"))
      (node (ref "D1") (pin "C") (pinfunction "C_C") (pintype "passive"))
      (node (ref "IC1") (pin "34") (pinfunction "VDD2_34") (pintype "power_in"))
      (node (ref "IC1") (pin "35") (pinfunction "VDD_35") (pintype "power_in"))
      (node (ref "U$5") (pin "P$1") (pinfunction "P$1_P$1") (pintype "passive"))
      (node (ref "U1") (pin "1") (pinfunction "IN_1") (pintype "input"))
      (node (ref "U1") (pin "3") (pinfunction "EN_3") (pintype "input"))
      (node (ref "U2") (pin "12") (pinfunction "VBOOST_12") (pintype "passive"))
    )
    (net (code "77") (name "unconnected-(U$2-VCC-Pad2)") (class "Default")
      (node (ref "U$2") (pin "2") (pinfunction "VCC_2") (pintype "power_in"))
    )
    (net (code "78") (name "unconnected-(U$3-2-Pad3)") (class "Default")
      (node (ref "U$3") (pin "3") (pinfunction "2_3") (pintype "passive"))
    )
    (net (code "79") (name "unconnected-(U$3-3-Pad4)") (class "Default")
      (node (ref "U$3") (pin "4") (pinfunction "3_4") (pintype "passive"))
    )
    (net (code "80") (name "unconnected-(U$12-VCC-Pad2)") (class "Default")
      (node (ref "U$12") (pin "2") (pinfunction "VCC_2") (pintype "power_in"))
    )
    (net (code "81") (name "unconnected-(U$13-VCC-Pad2)") (class "Default")
      (node (ref "U$13") (pin "2") (pinfunction "VCC_2") (pintype "power_in"))
    )
    (net (code "82") (name "unconnected-(U1-BP-Pad4)") (class "Default")
      (node (ref "U1") (pin "4") (pinfunction "BP_4") (pintype "input"))
    )
    (net (code "83") (name "unconnected-(U2-NC1-Pad40)") (class "Default")
      (node (ref "U2") (pin "40") (pinfunction "NC1_40") (pintype "passive"))
    )
    (net (code "84") (name "unconnected-(U2-NC2-Pad41)") (class "Default")
      (node (ref "U2") (pin "41") (pinfunction "NC2_41") (pintype "passive"))
    )
    (net (code "85") (name "unconnected-(U2-NC3-Pad57)") (class "Default")
      (node (ref "U2") (pin "57") (pinfunction "NC3_57") (pintype "passive"))
    )
    (net (code "86") (name "unconnected-(U2-NC4-Pad58)") (class "Default")
      (node (ref "U2") (pin "58") (pinfunction "NC4_58") (pintype "passive"))
    )
    (net (code "87") (name "unconnected-(U2-NC5-Pad59)") (class "Default")
      (node (ref "U2") (pin "59") (pinfunction "NC5_59") (pintype "passive"))
    )
    (net (code "88") (name "unconnected-(U2-NC6-Pad60)") (class "Default")
      (node (ref "U2") (pin "60") (pinfunction "NC6_60") (pintype "passive"))
    )
    (net (code "89") (name "unconnected-(U2-NC7-Pad61)") (class "Default")
      (node (ref "U2") (pin "61") (pinfunction "NC7_61") (pintype "passive"))
    )
    (net (code "90") (name "unconnected-(U2-NC8-Pad62)") (class "Default")
      (node (ref "U2") (pin "62") (pinfunction "NC8_62") (pintype "passive"))
    )
    (net (code "91") (name "unconnected-(U2-P0_4-Pad76)") (class "Default")
      (node (ref "U2") (pin "76") (pinfunction "P0_4_76") (pintype "passive"))
    )
    (net (code "92") (name "unconnected-(U2-P1_2-Pad22)") (class "Default")
      (node (ref "U2") (pin "22") (pinfunction "P1_2_22") (pintype "passive"))
    )
    (net (code "93") (name "unconnected-(U2-P1_5_NTRST-Pad25)") (class "Default")
      (node (ref "U2") (pin "25") (pinfunction "P1_5_NTRST_25") (pintype "passive"))
    )
    (net (code "94") (name "unconnected-(U2-P1_7-Pad28)") (class "Default")
      (node (ref "U2") (pin "28") (pinfunction "P1_7_28") (pintype "passive"))
    )
    (net (code "95") (name "unconnected-(U2-P2_5-Pad1)") (class "Default")
      (node (ref "U2") (pin "1") (pinfunction "P2_5_1") (pintype "passive"))
    )
    (net (code "96") (name "unconnected-(U2-P2_6-Pad2)") (class "Default")
      (node (ref "U2") (pin "2") (pinfunction "P2_6_2") (pintype "passive"))
    )
    (net (code "97") (name "unconnected-(U2-P2_7-Pad3)") (class "Default")
      (node (ref "U2") (pin "3") (pinfunction "P2_7_3") (pintype "passive"))
    )
    (net (code "98") (name "unconnected-(U2-P4_0-Pad69)") (class "Default")
      (node (ref "U2") (pin "69") (pinfunction "P4_0_69") (pintype "passive"))
    )
    (net (code "99") (name "unconnected-(U2-P4_2-Pad80)") (class "Default")
      (node (ref "U2") (pin "80") (pinfunction "P4_2_80") (pintype "passive"))
    )
    (net (code "100") (name "unconnected-(U2-P4_3-Pad81)") (class "Default")
      (node (ref "U2") (pin "81") (pinfunction "P4_3_81") (pintype "passive"))
    )
    (net (code "101") (name "unconnected-(U2-P4_4-Pad82)") (class "Default")
      (node (ref "U2") (pin "82") (pinfunction "P4_4_82") (pintype "passive"))
    )
    (net (code "102") (name "unconnected-(U2-P4_5-Pad83)") (class "Default")
      (node (ref "U2") (pin "83") (pinfunction "P4_5_83") (pintype "passive"))
    )
    (net (code "103") (name "unconnected-(U2-P4_6-Pad84)") (class "Default")
      (node (ref "U2") (pin "84") (pinfunction "P4_6_84") (pintype "passive"))
    )
    (net (code "104") (name "unconnected-(U2-P4_7-Pad85)") (class "Default")
      (node (ref "U2") (pin "85") (pinfunction "P4_7_85") (pintype "passive"))
    )
    (net (code "105") (name "unconnected-(U2-P5_4-Pad31)") (class "Default")
      (node (ref "U2") (pin "31") (pinfunction "P5_4_31") (pintype "passive"))
    )
    (net (code "106") (name "unconnected-(U2-P5_5-Pad32)") (class "Default")
      (node (ref "U2") (pin "32") (pinfunction "P5_5_32") (pintype "passive"))
    )
    (net (code "107") (name "unconnected-(U2-P6_0-Pad89)") (class "Default")
      (node (ref "U2") (pin "89") (pinfunction "P6_0_89") (pintype "passive"))
    )
    (net (code "108") (name "unconnected-(U2-P6_1-Pad90)") (class "Default")
      (node (ref "U2") (pin "90") (pinfunction "P6_1_90") (pintype "passive"))
    )
    (net (code "109") (name "unconnected-(U2-P6_2-Pad91)") (class "Default")
      (node (ref "U2") (pin "91") (pinfunction "P6_2_91") (pintype "passive"))
    )
    (net (code "110") (name "unconnected-(U2-P6_3-Pad92)") (class "Default")
      (node (ref "U2") (pin "92") (pinfunction "P6_3_92") (pintype "passive"))
    )
    (net (code "111") (name "unconnected-(U2-P6_4-Pad6)") (class "Default")
      (node (ref "U2") (pin "6") (pinfunction "P6_4_6") (pintype "passive"))
    )
    (net (code "112") (name "unconnected-(U2-P6_5-Pad7)") (class "Default")
      (node (ref "U2") (pin "7") (pinfunction "P6_5_7") (pintype "passive"))
    )
    (net (code "113") (name "unconnected-(U2-P6_6-Pad8)") (class "Default")
      (node (ref "U2") (pin "8") (pinfunction "P6_6_8") (pintype "passive"))
    )
    (net (code "114") (name "unconnected-(U2-P6_7-Pad9)") (class "Default")
      (node (ref "U2") (pin "9") (pinfunction "P6_7_9") (pintype "passive"))
    )
    (net (code "115") (name "unconnected-(U2-P15_2_KXO-Pad55)") (class "Default")
      (node (ref "U2") (pin "55") (pinfunction "P15_2_KXO_55") (pintype "passive"))
    )
    (net (code "116") (name "unconnected-(U2-P15_3_KXI-Pad56)") (class "Default")
      (node (ref "U2") (pin "56") (pinfunction "P15_3_KXI_56") (pintype "passive"))
    )
    (net (code "117") (name "unconnected-(U2-P15_4-Pad93)") (class "Default")
      (node (ref "U2") (pin "93") (pinfunction "P15_4_93") (pintype "passive"))
    )
    (net (code "118") (name "unconnected-(U2-P15_5-Pad94)") (class "Default")
      (node (ref "U2") (pin "94") (pinfunction "P15_5_94") (pintype "passive"))
    )
    (net (code "119") (name "unconnected-(U7-PadID)") (class "Default")
      (node (ref "U7") (pin "ID") (pinfunction "ID_ID") (pintype "bidirectional"))
    )
    (net (code "120") (name "unconnected-(U7-SH-PadSH1)") (class "Default")
      (node (ref "U7") (pin "SH1") (pinfunction "SH_SH1") (pintype "bidirectional"))
    )
    (net (code "121") (name "unconnected-(U7-SH-PadSH2)") (class "Default")
      (node (ref "U7") (pin "SH2") (pinfunction "SH_SH2") (pintype "bidirectional"))
    )
    (net (code "122") (name "unconnected-(U7-SH-PadSH3)") (class "Default")
      (node (ref "U7") (pin "SH3") (pinfunction "SH_SH3") (pintype "bidirectional"))
    )
    (net (code "123") (name "unconnected-(U7-SH-PadSH4)") (class "Default")
      (node (ref "U7") (pin "SH4") (pinfunction "SH_SH4") (pintype "bidirectional"))
    )
    (net (code "124") (name "unconnected-(U7-SH-PadSH5)") (class "Default")
      (node (ref "U7") (pin "SH5") (pinfunction "SH_SH5") (pintype "bidirectional"))
    )
    (net (code "125") (name "unconnected-(U7-SH-PadSH6)") (class "Default")
      (node (ref "U7") (pin "SH6") (pinfunction "SH_SH6") (pintype "bidirectional"))
    )
  )
)
